# schematic.net
KiCad netlist of a schematic drawn in EasyEDA
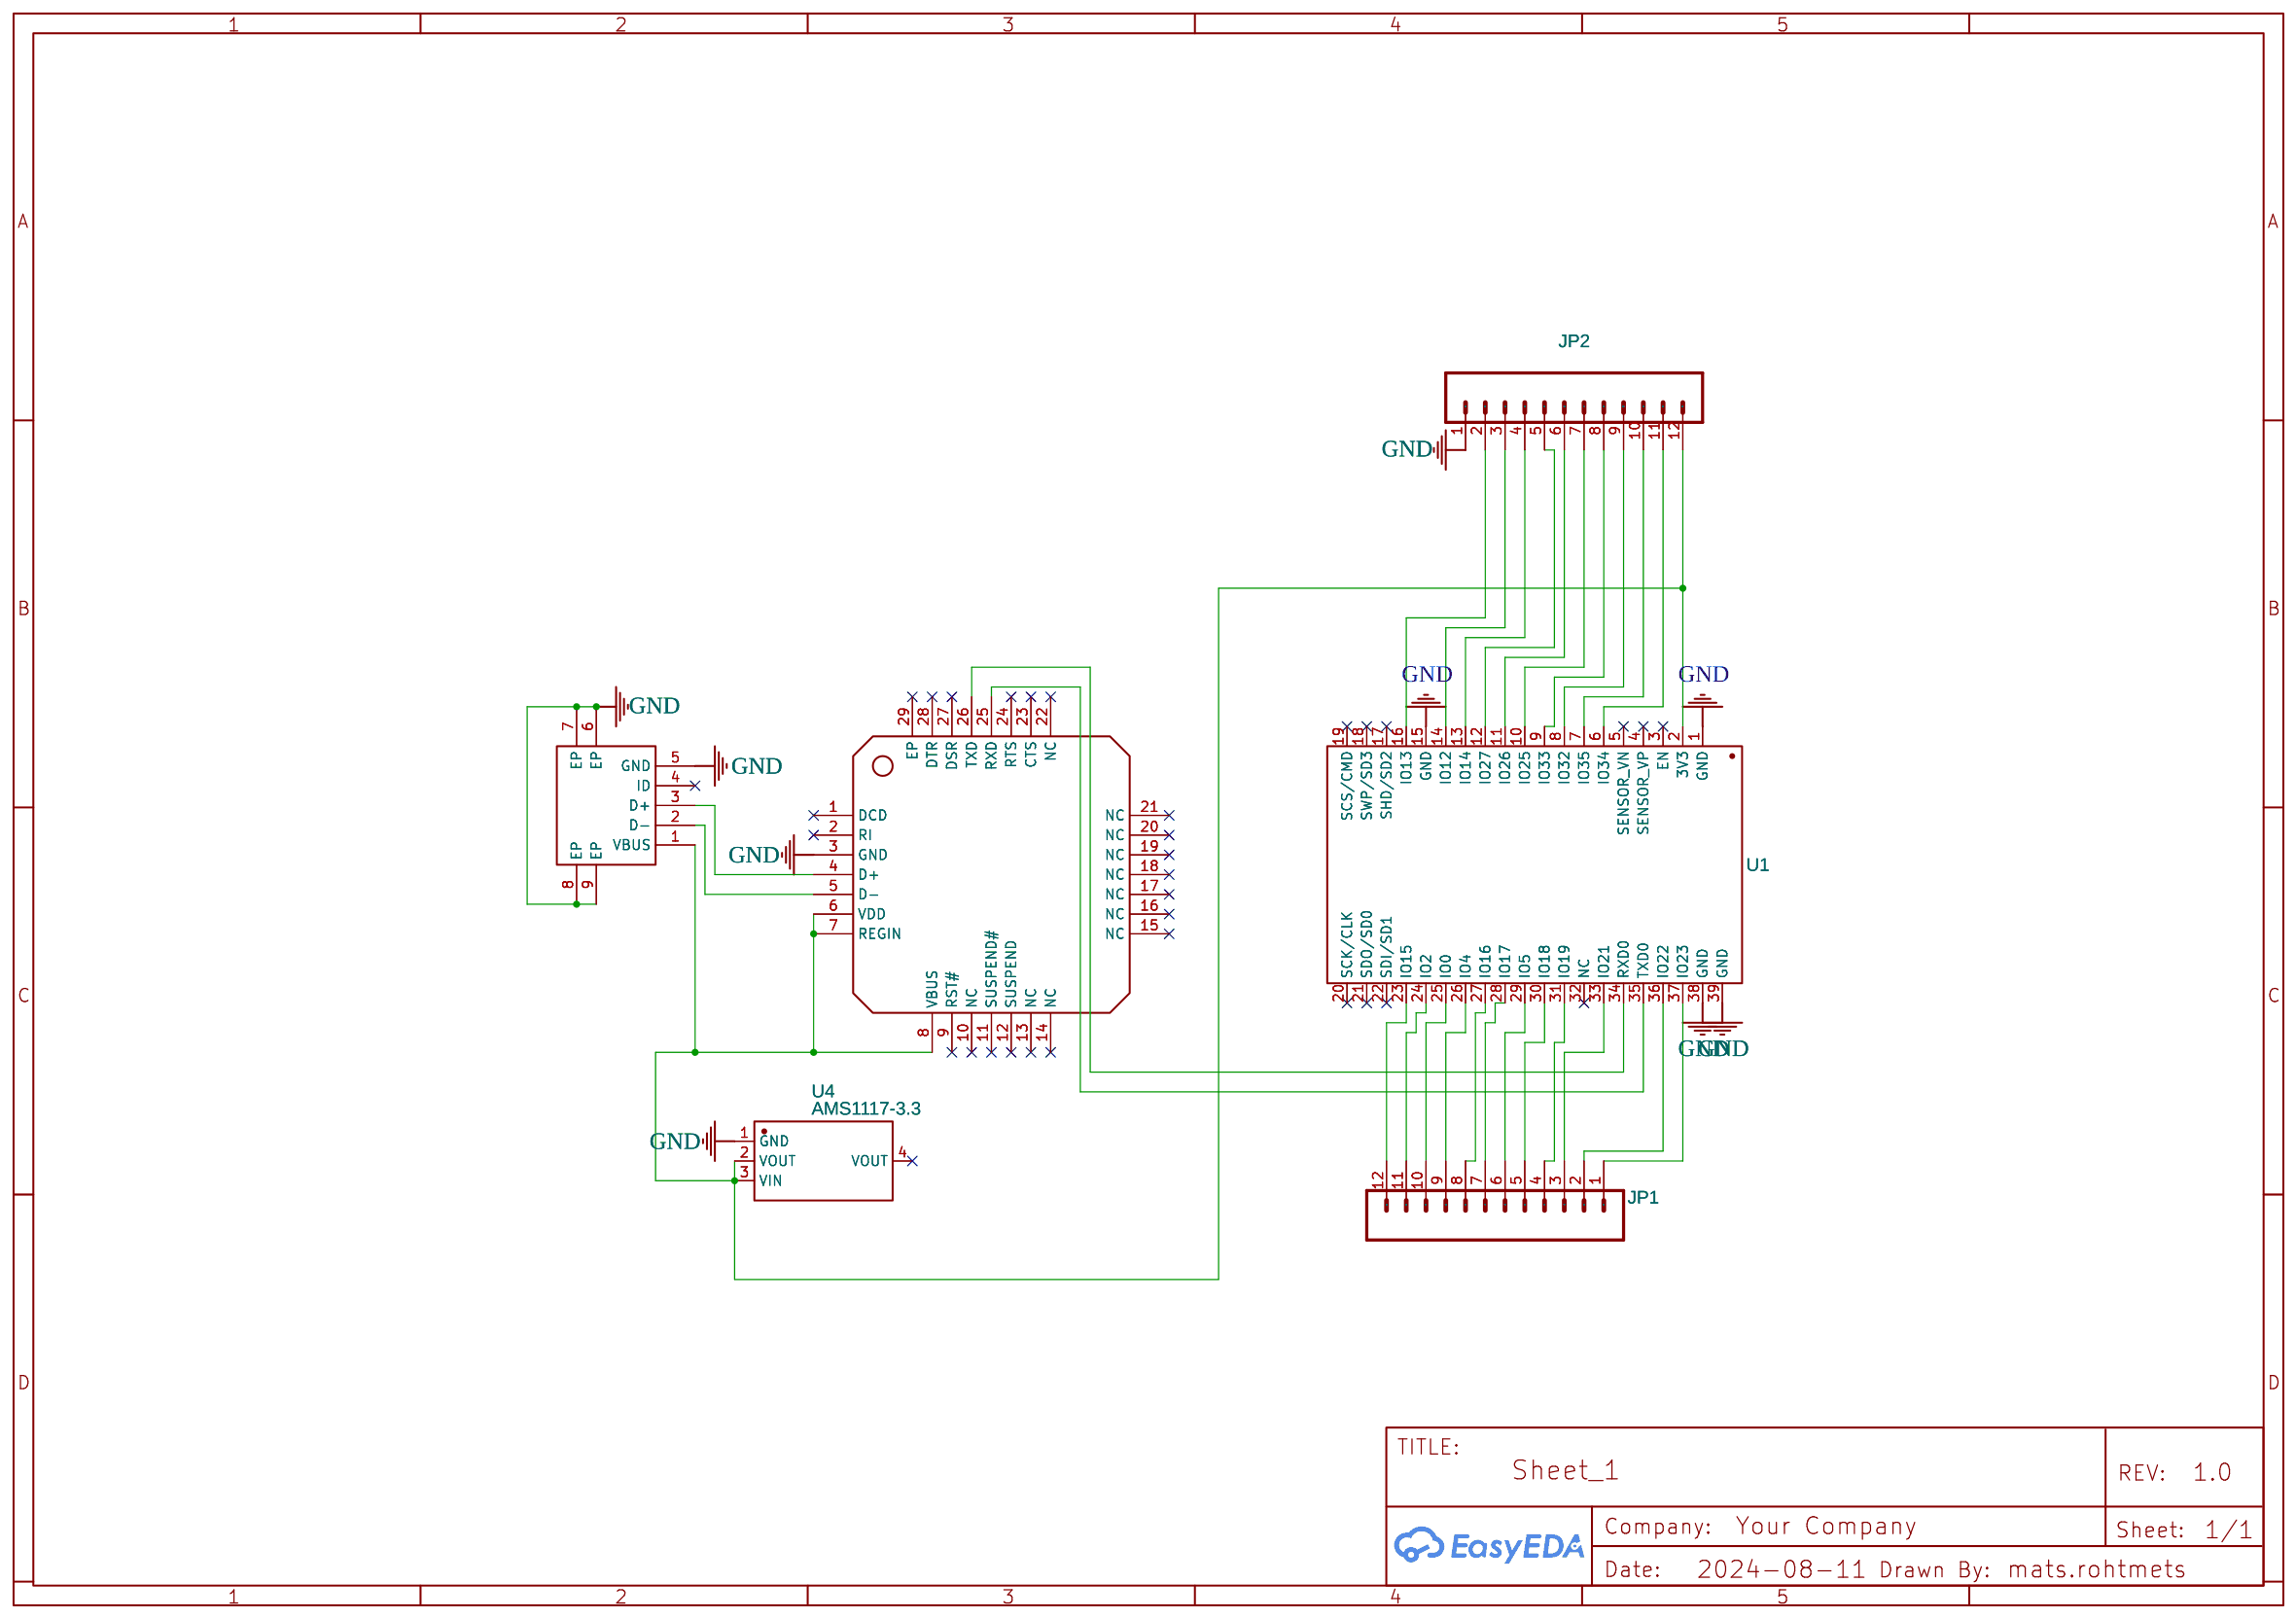
[diagram p0: schematic sheet]

(export (version "E")
  (design (tool "Eeschema 10.0.6"))
  (components
    (comp (ref "JP1")
      (value "M12MACHINE-PIN_LOCK")
      (fields
        (field (name "Manufacturer Part") "HC-PM254-8.5H-1x12PZ")
        (field (name "Manufacturer") "Hong Cheng")
      )
      (libsource (lib "") (part "M12MACHINE-PIN_LOCK_1"))
    )
    (comp (ref "JP2")
      (value "M12MACHINE-PIN_LOCK")
      (fields
        (field (name "Manufacturer Part") "HC-PM254-8.5H-1x12PZ")
        (field (name "Manufacturer") "Hong Cheng")
      )
      (libsource (lib "") (part "M12MACHINE-PIN_LOCK"))
    )
    (comp (ref "U1")
      (value "ESP32-WROOM-32")
      (fields
        (field (name "Manufacturer Part") "ESP32-WROOM-32-N4")
        (field (name "Manufacturer") "ESPRESSIF(乐鑫)")
      )
      (libsource (lib "") (part "ESP32-WROOM-32"))
    )
    (comp (ref "U3")
      (value "CP2102-GMR")
      (fields (field (name "Manufacturer") "SKYWORKS/SILICON LABS(芯科)"))
      (libsource (lib "") (part "CP2102-GMR"))
    )
    (comp (ref "U4")
      (value "AMS1117-3.3")
      (fields (field (name "Manufacturer") "AMS"))
      (libsource (lib "") (part "AMS1117-3.3"))
    )
    (comp (ref "USB1")
      (value "MICRO 7.2JB")
      (fields (field (name "Manufacturer") "SHOU HAN(首韩)"))
      (libsource (lib "") (part "MICRO 7.2JB"))
    )
  )
  (nets
    (net (code "1") (name "GND") (class "Default")
      (node (ref "JP2") (pin "1") (pinfunction "1_1") (pintype "bidirectional"))
      (node (ref "U1") (pin "1") (pinfunction "GND_1") (pintype "unspecified"))
      (node (ref "U1") (pin "15") (pinfunction "GND_15") (pintype "unspecified"))
      (node (ref "U1") (pin "38") (pinfunction "GND_38") (pintype "unspecified"))
      (node (ref "U1") (pin "39") (pinfunction "GND_39") (pintype "unspecified"))
      (node (ref "U3") (pin "3") (pinfunction "GND_3") (pintype "unspecified"))
      (node (ref "U4") (pin "1") (pinfunction "GND_1") (pintype "unspecified"))
      (node (ref "USB1") (pin "5") (pinfunction "GND_5") (pintype "unspecified"))
      (node (ref "USB1") (pin "6") (pinfunction "EP_6") (pintype "unspecified"))
      (node (ref "USB1") (pin "7") (pinfunction "EP_7") (pintype "unspecified"))
      (node (ref "USB1") (pin "8") (pinfunction "EP_8") (pintype "unspecified"))
      (node (ref "USB1") (pin "9") (pinfunction "EP_9") (pintype "unspecified"))
    )
    (net (code "2") (name "Net-(U1-3V3)") (class "Default")
      (node (ref "JP2") (pin "12") (pinfunction "12_12") (pintype "bidirectional"))
      (node (ref "U1") (pin "2") (pinfunction "3V3_2") (pintype "unspecified"))
      (node (ref "U3") (pin "6") (pinfunction "VDD_6") (pintype "unspecified"))
      (node (ref "U3") (pin "7") (pinfunction "REGIN_7") (pintype "unspecified"))
      (node (ref "U3") (pin "8") (pinfunction "VBUS_8") (pintype "unspecified"))
      (node (ref "U4") (pin "2") (pinfunction "VOUT_2") (pintype "unspecified"))
      (node (ref "U4") (pin "3") (pinfunction "VIN_3") (pintype "unspecified"))
      (node (ref "USB1") (pin "1") (pinfunction "VBUS_1") (pintype "unspecified"))
    )
    (net (code "3") (name "Net-(U1-IO0)") (class "Default")
      (node (ref "JP1") (pin "10") (pinfunction "10_10") (pintype "bidirectional"))
      (node (ref "U1") (pin "25") (pinfunction "IO0_25") (pintype "unspecified"))
    )
    (net (code "4") (name "Net-(U1-IO2)") (class "Default")
      (node (ref "JP1") (pin "11") (pinfunction "11_11") (pintype "bidirectional"))
      (node (ref "U1") (pin "24") (pinfunction "IO2_24") (pintype "unspecified"))
    )
    (net (code "5") (name "Net-(U1-IO4)") (class "Default")
      (node (ref "JP1") (pin "9") (pinfunction "9_9") (pintype "bidirectional"))
      (node (ref "U1") (pin "26") (pinfunction "IO4_26") (pintype "unspecified"))
    )
    (net (code "6") (name "Net-(U1-IO5)") (class "Default")
      (node (ref "JP1") (pin "6") (pinfunction "6_6") (pintype "bidirectional"))
      (node (ref "U1") (pin "29") (pinfunction "IO5_29") (pintype "unspecified"))
    )
    (net (code "7") (name "Net-(U1-IO12)") (class "Default")
      (node (ref "JP2") (pin "3") (pinfunction "3_3") (pintype "bidirectional"))
      (node (ref "U1") (pin "14") (pinfunction "IO12_14") (pintype "unspecified"))
    )
    (net (code "8") (name "Net-(U1-IO13)") (class "Default")
      (node (ref "JP2") (pin "2") (pinfunction "2_2") (pintype "bidirectional"))
      (node (ref "U1") (pin "16") (pinfunction "IO13_16") (pintype "unspecified"))
    )
    (net (code "9") (name "Net-(U1-IO14)") (class "Default")
      (node (ref "JP2") (pin "4") (pinfunction "4_4") (pintype "bidirectional"))
      (node (ref "U1") (pin "13") (pinfunction "IO14_13") (pintype "unspecified"))
    )
    (net (code "10") (name "Net-(U1-IO15)") (class "Default")
      (node (ref "JP1") (pin "12") (pinfunction "12_12") (pintype "bidirectional"))
      (node (ref "U1") (pin "23") (pinfunction "IO15_23") (pintype "unspecified"))
    )
    (net (code "11") (name "Net-(U1-IO16)") (class "Default")
      (node (ref "JP1") (pin "8") (pinfunction "8_8") (pintype "bidirectional"))
      (node (ref "U1") (pin "27") (pinfunction "IO16_27") (pintype "unspecified"))
    )
    (net (code "12") (name "Net-(U1-IO17)") (class "Default")
      (node (ref "JP1") (pin "7") (pinfunction "7_7") (pintype "bidirectional"))
      (node (ref "U1") (pin "28") (pinfunction "IO17_28") (pintype "unspecified"))
    )
    (net (code "13") (name "Net-(U1-IO18)") (class "Default")
      (node (ref "JP1") (pin "5") (pinfunction "5_5") (pintype "bidirectional"))
      (node (ref "U1") (pin "30") (pinfunction "IO18_30") (pintype "unspecified"))
    )
    (net (code "14") (name "Net-(U1-IO19)") (class "Default")
      (node (ref "JP1") (pin "4") (pinfunction "4_4") (pintype "bidirectional"))
      (node (ref "U1") (pin "31") (pinfunction "IO19_31") (pintype "unspecified"))
    )
    (net (code "15") (name "Net-(U1-IO21)") (class "Default")
      (node (ref "JP1") (pin "3") (pinfunction "3_3") (pintype "bidirectional"))
      (node (ref "U1") (pin "33") (pinfunction "IO21_33") (pintype "unspecified"))
    )
    (net (code "16") (name "Net-(U1-IO22)") (class "Default")
      (node (ref "JP1") (pin "2") (pinfunction "2_2") (pintype "bidirectional"))
      (node (ref "U1") (pin "36") (pinfunction "IO22_36") (pintype "unspecified"))
    )
    (net (code "17") (name "Net-(U1-IO23)") (class "Default")
      (node (ref "JP1") (pin "1") (pinfunction "1_1") (pintype "bidirectional"))
      (node (ref "U1") (pin "37") (pinfunction "IO23_37") (pintype "unspecified"))
    )
    (net (code "18") (name "Net-(U1-IO25)") (class "Default")
      (node (ref "JP2") (pin "7") (pinfunction "7_7") (pintype "bidirectional"))
      (node (ref "U1") (pin "10") (pinfunction "IO25_10") (pintype "unspecified"))
    )
    (net (code "19") (name "Net-(U1-IO26)") (class "Default")
      (node (ref "JP2") (pin "6") (pinfunction "6_6") (pintype "bidirectional"))
      (node (ref "U1") (pin "11") (pinfunction "IO26_11") (pintype "unspecified"))
    )
    (net (code "20") (name "Net-(U1-IO27)") (class "Default")
      (node (ref "JP2") (pin "5") (pinfunction "5_5") (pintype "bidirectional"))
      (node (ref "U1") (pin "12") (pinfunction "IO27_12") (pintype "unspecified"))
    )
    (net (code "21") (name "Net-(U1-IO32)") (class "Default")
      (node (ref "JP2") (pin "9") (pinfunction "9_9") (pintype "bidirectional"))
      (node (ref "U1") (pin "8") (pinfunction "IO32_8") (pintype "unspecified"))
    )
    (net (code "22") (name "Net-(U1-IO33)") (class "Default")
      (node (ref "JP2") (pin "8") (pinfunction "8_8") (pintype "bidirectional"))
      (node (ref "U1") (pin "9") (pinfunction "IO33_9") (pintype "unspecified"))
    )
    (net (code "23") (name "Net-(U1-IO34)") (class "Default")
      (node (ref "JP2") (pin "11") (pinfunction "11_11") (pintype "bidirectional"))
      (node (ref "U1") (pin "6") (pinfunction "IO34_6") (pintype "unspecified"))
    )
    (net (code "24") (name "Net-(U1-IO35)") (class "Default")
      (node (ref "JP2") (pin "10") (pinfunction "10_10") (pintype "bidirectional"))
      (node (ref "U1") (pin "7") (pinfunction "IO35_7") (pintype "unspecified"))
    )
    (net (code "25") (name "Net-(U1-RXD0)") (class "Default")
      (node (ref "U1") (pin "34") (pinfunction "RXD0_34") (pintype "unspecified"))
      (node (ref "U3") (pin "26") (pinfunction "TXD_26") (pintype "unspecified"))
    )
    (net (code "26") (name "Net-(U1-TXD0)") (class "Default")
      (node (ref "U1") (pin "35") (pinfunction "TXD0_35") (pintype "unspecified"))
      (node (ref "U3") (pin "25") (pinfunction "RXD_25") (pintype "unspecified"))
    )
    (net (code "27") (name "Net-(U3-D+)") (class "Default")
      (node (ref "U3") (pin "4") (pinfunction "D+_4") (pintype "unspecified"))
      (node (ref "USB1") (pin "3") (pinfunction "D+_3") (pintype "unspecified"))
    )
    (net (code "28") (name "Net-(U3-D-)") (class "Default")
      (node (ref "U3") (pin "5") (pinfunction "D-_5") (pintype "unspecified"))
      (node (ref "USB1") (pin "2") (pinfunction "D-_2") (pintype "unspecified"))
    )
    (net (code "29") (name "unconnected-(U1-EN-Pad3)") (class "Default")
      (node (ref "U1") (pin "3") (pinfunction "EN_3") (pintype "unspecified+no_connect"))
    )
    (net (code "30") (name "unconnected-(U1-NC-Pad32)") (class "Default")
      (node (ref "U1") (pin "32") (pinfunction "NC_32") (pintype "unspecified+no_connect"))
    )
    (net (code "31") (name "unconnected-(U1-SCK{slash}CLK-Pad20)") (class "Default")
      (node (ref "U1") (pin "20") (pinfunction "SCK/CLK_20") (pintype "unspecified+no_connect"))
    )
    (net (code "32") (name "unconnected-(U1-SCS{slash}CMD-Pad19)") (class "Default")
      (node (ref "U1") (pin "19") (pinfunction "SCS/CMD_19") (pintype "unspecified+no_connect"))
    )
    (net (code "33") (name "unconnected-(U1-SDI{slash}SD1-Pad22)") (class "Default")
      (node (ref "U1") (pin "22") (pinfunction "SDI/SD1_22") (pintype "unspecified+no_connect"))
    )
    (net (code "34") (name "unconnected-(U1-SDO{slash}SD0-Pad21)") (class "Default")
      (node (ref "U1") (pin "21") (pinfunction "SDO/SD0_21") (pintype "unspecified+no_connect"))
    )
    (net (code "35") (name "unconnected-(U1-SENSOR_VN-Pad5)") (class "Default")
      (node (ref "U1") (pin "5") (pinfunction "SENSOR_VN_5") (pintype "unspecified+no_connect"))
    )
    (net (code "36") (name "unconnected-(U1-SENSOR_VP-Pad4)") (class "Default")
      (node (ref "U1") (pin "4") (pinfunction "SENSOR_VP_4") (pintype "unspecified+no_connect"))
    )
    (net (code "37") (name "unconnected-(U1-SHD{slash}SD2-Pad17)") (class "Default")
      (node (ref "U1") (pin "17") (pinfunction "SHD/SD2_17") (pintype "unspecified+no_connect"))
    )
    (net (code "38") (name "unconnected-(U1-SWP{slash}SD3-Pad18)") (class "Default")
      (node (ref "U1") (pin "18") (pinfunction "SWP/SD3_18") (pintype "unspecified+no_connect"))
    )
    (net (code "39") (name "unconnected-(U3-CTS-Pad23)") (class "Default")
      (node (ref "U3") (pin "23") (pinfunction "CTS_23") (pintype "unspecified+no_connect"))
    )
    (net (code "40") (name "unconnected-(U3-DCD-Pad1)") (class "Default")
      (node (ref "U3") (pin "1") (pinfunction "DCD_1") (pintype "unspecified+no_connect"))
    )
    (net (code "41") (name "unconnected-(U3-DSR-Pad27)") (class "Default")
      (node (ref "U3") (pin "27") (pinfunction "DSR_27") (pintype "unspecified+no_connect"))
    )
    (net (code "42") (name "unconnected-(U3-DTR-Pad28)") (class "Default")
      (node (ref "U3") (pin "28") (pinfunction "DTR_28") (pintype "unspecified+no_connect"))
    )
    (net (code "43") (name "unconnected-(U3-EP-Pad29)") (class "Default")
      (node (ref "U3") (pin "29") (pinfunction "EP_29") (pintype "unspecified+no_connect"))
    )
    (net (code "44") (name "unconnected-(U3-NC-Pad10)") (class "Default")
      (node (ref "U3") (pin "10") (pinfunction "NC_10") (pintype "unspecified+no_connect"))
    )
    (net (code "45") (name "unconnected-(U3-NC-Pad13)") (class "Default")
      (node (ref "U3") (pin "13") (pinfunction "NC_13") (pintype "unspecified+no_connect"))
    )
    (net (code "46") (name "unconnected-(U3-NC-Pad14)") (class "Default")
      (node (ref "U3") (pin "14") (pinfunction "NC_14") (pintype "unspecified+no_connect"))
    )
    (net (code "47") (name "unconnected-(U3-NC-Pad15)") (class "Default")
      (node (ref "U3") (pin "15") (pinfunction "NC_15") (pintype "unspecified+no_connect"))
    )
    (net (code "48") (name "unconnected-(U3-NC-Pad16)") (class "Default")
      (node (ref "U3") (pin "16") (pinfunction "NC_16") (pintype "unspecified+no_connect"))
    )
    (net (code "49") (name "unconnected-(U3-NC-Pad17)") (class "Default")
      (node (ref "U3") (pin "17") (pinfunction "NC_17") (pintype "unspecified+no_connect"))
    )
    (net (code "50") (name "unconnected-(U3-NC-Pad18)") (class "Default")
      (node (ref "U3") (pin "18") (pinfunction "NC_18") (pintype "unspecified+no_connect"))
    )
    (net (code "51") (name "unconnected-(U3-NC-Pad19)") (class "Default")
      (node (ref "U3") (pin "19") (pinfunction "NC_19") (pintype "unspecified+no_connect"))
    )
    (net (code "52") (name "unconnected-(U3-NC-Pad20)") (class "Default")
      (node (ref "U3") (pin "20") (pinfunction "NC_20") (pintype "unspecified+no_connect"))
    )
    (net (code "53") (name "unconnected-(U3-NC-Pad21)") (class "Default")
      (node (ref "U3") (pin "21") (pinfunction "NC_21") (pintype "unspecified+no_connect"))
    )
    (net (code "54") (name "unconnected-(U3-NC-Pad22)") (class "Default")
      (node (ref "U3") (pin "22") (pinfunction "NC_22") (pintype "unspecified+no_connect"))
    )
    (net (code "55") (name "unconnected-(U3-RI-Pad2)") (class "Default")
      (node (ref "U3") (pin "2") (pinfunction "RI_2") (pintype "unspecified+no_connect"))
    )
    (net (code "56") (name "unconnected-(U3-RST#-Pad9)") (class "Default")
      (node (ref "U3") (pin "9") (pinfunction "RST#_9") (pintype "unspecified+no_connect"))
    )
    (net (code "57") (name "unconnected-(U3-RTS-Pad24)") (class "Default")
      (node (ref "U3") (pin "24") (pinfunction "RTS_24") (pintype "unspecified+no_connect"))
    )
    (net (code "58") (name "unconnected-(U3-SUSPEND#-Pad11)") (class "Default")
      (node (ref "U3") (pin "11") (pinfunction "SUSPEND#_11") (pintype "unspecified+no_connect"))
    )
    (net (code "59") (name "unconnected-(U3-SUSPEND-Pad12)") (class "Default")
      (node (ref "U3") (pin "12") (pinfunction "SUSPEND_12") (pintype "unspecified+no_connect"))
    )
    (net (code "60") (name "unconnected-(U4-VOUT-Pad4)") (class "Default")
      (node (ref "U4") (pin "4") (pinfunction "VOUT_4") (pintype "unspecified+no_connect"))
    )
    (net (code "61") (name "unconnected-(USB1-ID-Pad4)") (class "Default")
      (node (ref "USB1") (pin "4") (pinfunction "ID_4") (pintype "unspecified+no_connect"))
    )
  )
)
